# IO_Board.net
KiCad netlist of a schematic drawn in EAGLE
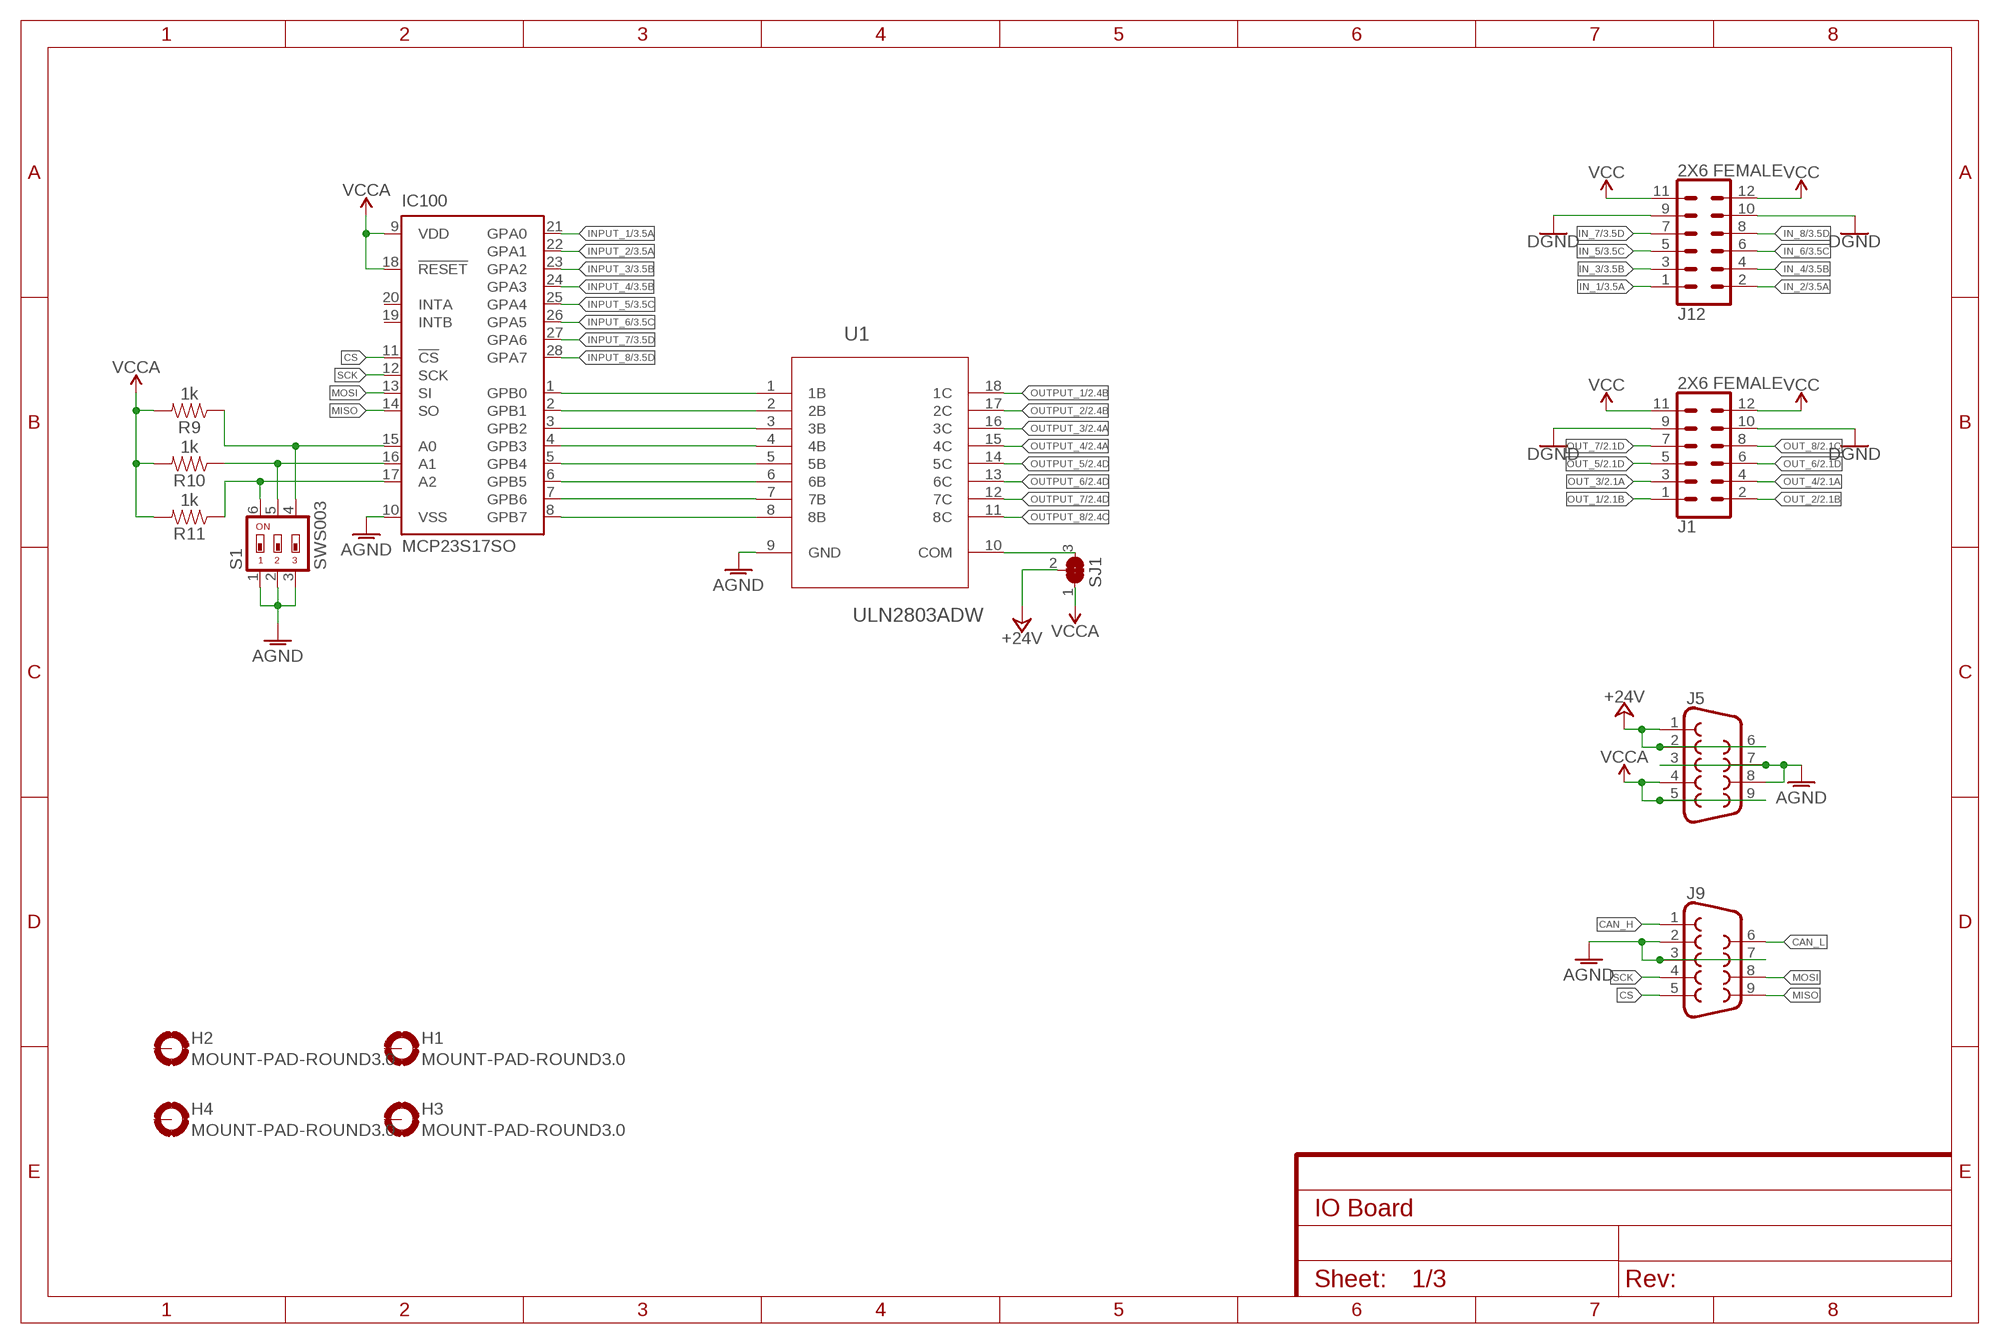
[diagram p0: schematic, sheet 1]
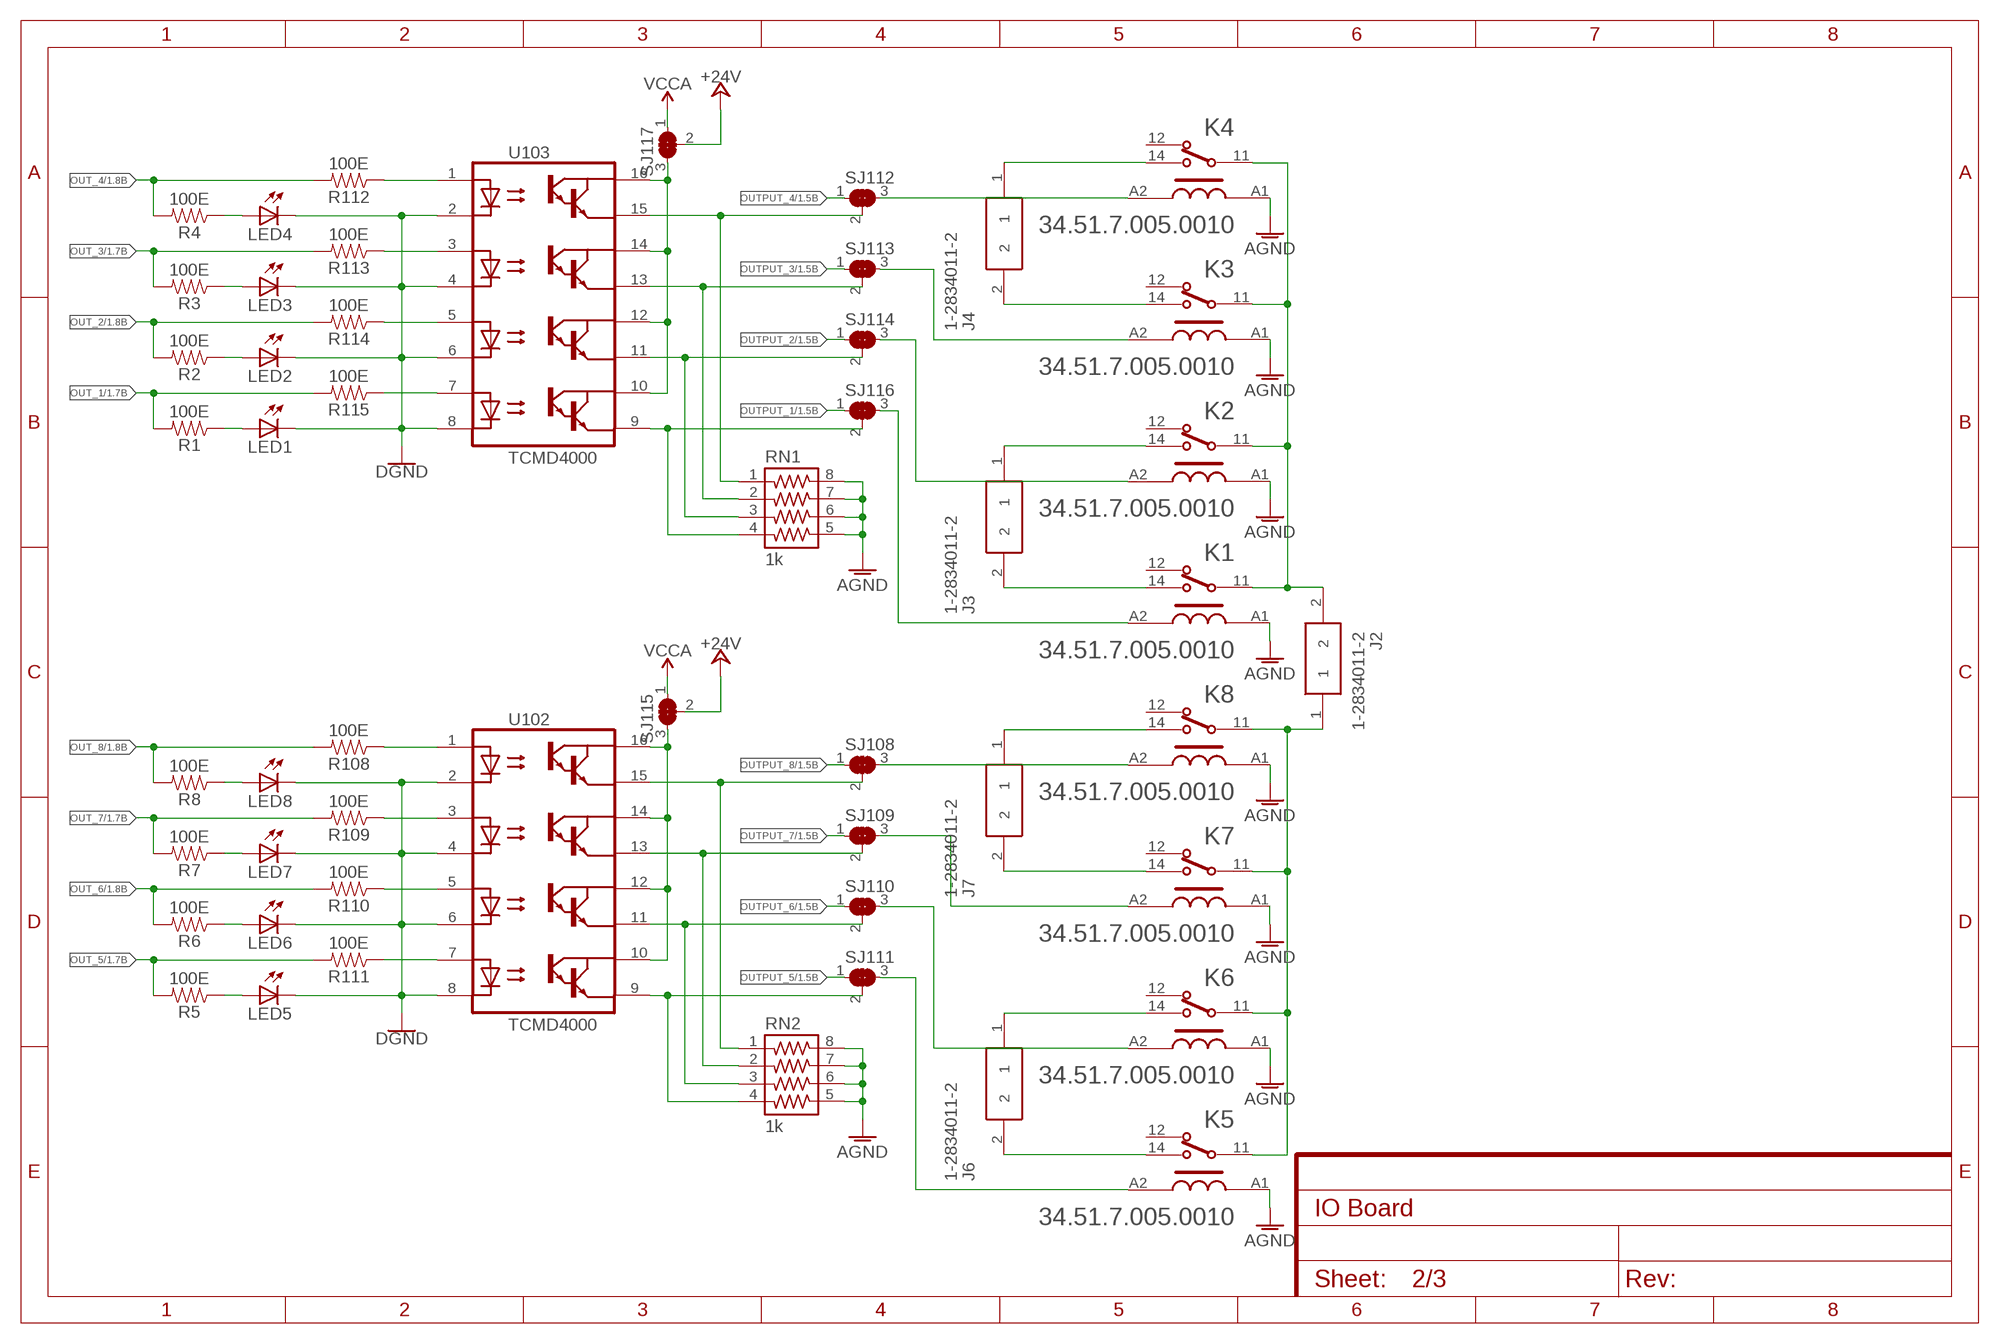
[diagram p1: schematic, sheet 2]
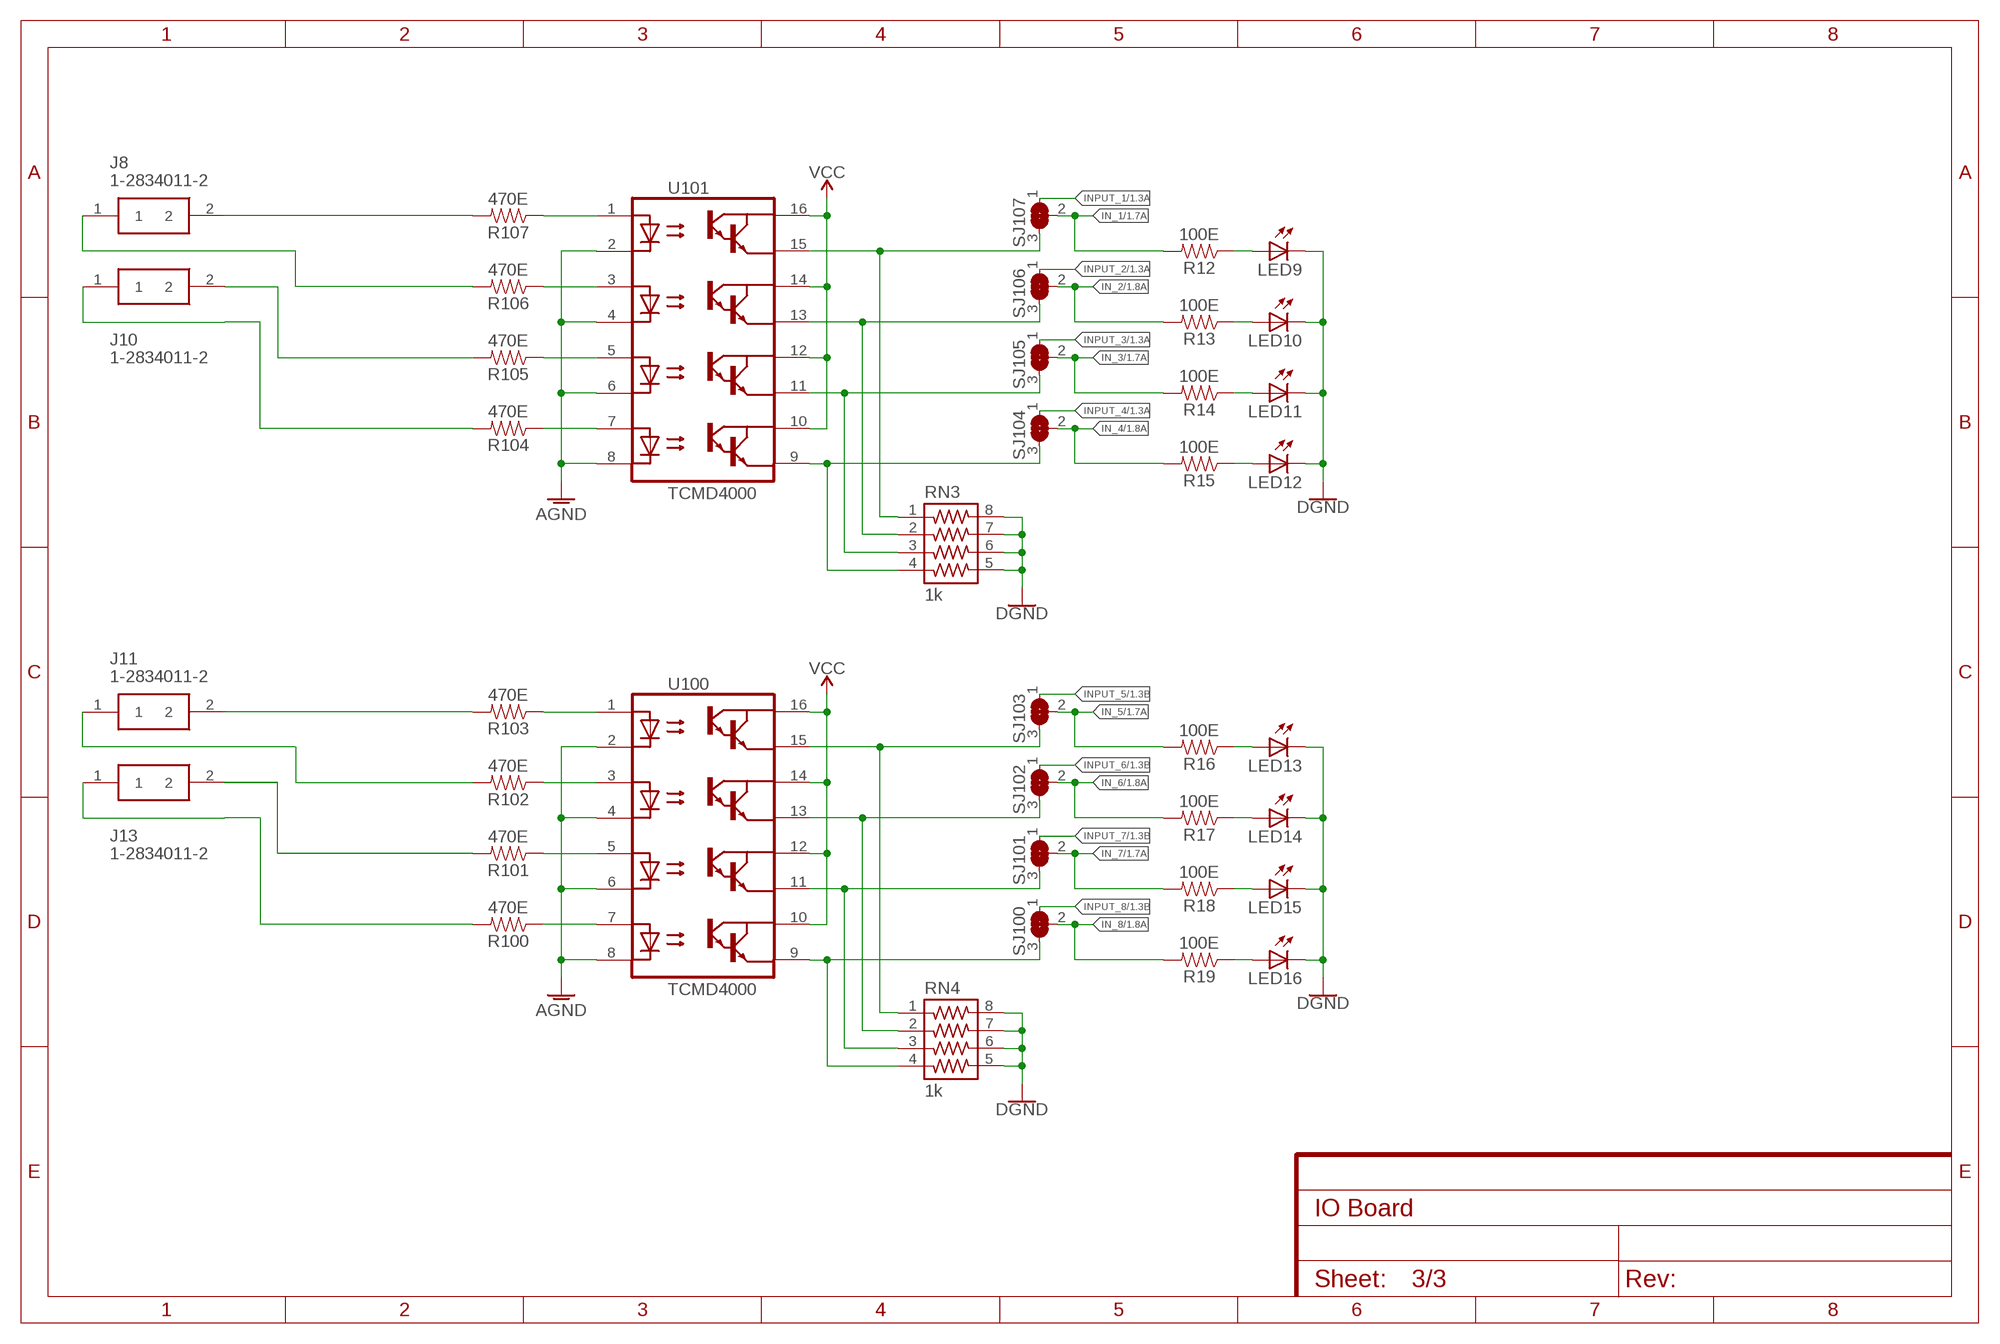
[diagram p2: schematic, sheet 3]

(export (version "E")
  (design (tool "Eeschema 10.0.6"))
  (components
    (comp (ref "H1")
      (value "MOUNT-PAD-ROUND3.0")
      (footprint "eagle-import:3,0-PAD")
      (libsource (lib "eagle-import") (part "MOUNT-PAD-ROUND3.0"))
    )
    (comp (ref "H2")
      (value "MOUNT-PAD-ROUND3.0")
      (footprint "eagle-import:3,0-PAD")
      (libsource (lib "eagle-import") (part "MOUNT-PAD-ROUND3.0"))
    )
    (comp (ref "H3")
      (value "MOUNT-PAD-ROUND3.0")
      (footprint "eagle-import:3,0-PAD")
      (libsource (lib "eagle-import") (part "MOUNT-PAD-ROUND3.0"))
    )
    (comp (ref "H4")
      (value "MOUNT-PAD-ROUND3.0")
      (footprint "eagle-import:3,0-PAD")
      (libsource (lib "eagle-import") (part "MOUNT-PAD-ROUND3.0"))
    )
    (comp (ref "IC100")
      (value "MCP23S17SO")
      (footprint "eagle-import:SO28W")
      (fields (field (name "MF") "MICROCHIP") (field (name "MPN") "MCP23S17-E/SO"))
      (libsource (lib "eagle-import") (part "MCP23S17SO"))
    )
    (comp (ref "J1")
      (value "2X6 FEMALE")
      (footprint "eagle-import:2X6")
      (libsource (lib "eagle-import") (part "CONN_06X2PTH_FEMALE"))
    )
    (comp (ref "J5")
      (value "DB9FEMALE")
      (footprint "eagle-import:DB9")
      (libsource (lib "eagle-import") (part "DB9FEMALE"))
    )
    (comp (ref "J9")
      (value "DB9FEMALE")
      (footprint "eagle-import:DB9")
      (libsource (lib "eagle-import") (part "DB9FEMALE"))
    )
    (comp (ref "J12")
      (value "2X6 FEMALE")
      (footprint "eagle-import:2X6")
      (libsource (lib "eagle-import") (part "CONN_06X2PTH_FEMALE"))
    )
    (comp (ref "R9")
      (value "1k")
      (footprint "eagle-import:0805")
      (libsource (lib "eagle-import") (part "RESISTOR0805"))
    )
    (comp (ref "R10")
      (value "1k")
      (footprint "eagle-import:0805")
      (libsource (lib "eagle-import") (part "RESISTOR0805"))
    )
    (comp (ref "R11")
      (value "1k")
      (footprint "eagle-import:0805")
      (libsource (lib "eagle-import") (part "RESISTOR0805"))
    )
    (comp (ref "S1")
      (value "SWS003")
      (footprint "eagle-import:SMS-003")
      (libsource (lib "eagle-import") (part "SWS003"))
    )
    (comp (ref "SJ1")
      (value "SOLDERJUMPER_2WAY")
      (footprint "eagle-import:SOLDERJUMPER_2WAY_OPEN_NOPASTE")
      (libsource (lib "eagle-import") (part "SOLDERJUMPER_2WAY"))
    )
    (comp (ref "U1")
      (value "ULN2803ADW")
      (footprint "eagle-import:SOIC127P1030X265-18N")
      (libsource (lib "eagle-import") (part "ULN2803ADW"))
    )
    (comp (ref "J8")
      (value "1-2834011-2")
      (footprint "eagle-import:128340112")
      (fields (field (name "RS_PART_NUMBER") "1649131"))
      (libsource (lib "eagle-import") (part "1-2834011-2"))
    )
    (comp (ref "J10")
      (value "1-2834011-2")
      (footprint "eagle-import:128340112")
      (fields (field (name "RS_PART_NUMBER") "1649131"))
      (libsource (lib "eagle-import") (part "1-2834011-2"))
    )
    (comp (ref "J11")
      (value "1-2834011-2")
      (footprint "eagle-import:128340112")
      (fields (field (name "RS_PART_NUMBER") "1649131"))
      (libsource (lib "eagle-import") (part "1-2834011-2"))
    )
    (comp (ref "J13")
      (value "1-2834011-2")
      (footprint "eagle-import:128340112")
      (fields (field (name "RS_PART_NUMBER") "1649131"))
      (libsource (lib "eagle-import") (part "1-2834011-2"))
    )
    (comp (ref "LED9")
      (value "LEDCHIP-LED0805")
      (footprint "eagle-import:CHIP-LED0805")
      (libsource (lib "eagle-import") (part "LEDCHIP-LED0805"))
    )
    (comp (ref "LED10")
      (value "LEDCHIP-LED0805")
      (footprint "eagle-import:CHIP-LED0805")
      (libsource (lib "eagle-import") (part "LEDCHIP-LED0805"))
    )
    (comp (ref "LED11")
      (value "LEDCHIP-LED0805")
      (footprint "eagle-import:CHIP-LED0805")
      (libsource (lib "eagle-import") (part "LEDCHIP-LED0805"))
    )
    (comp (ref "LED12")
      (value "LEDCHIP-LED0805")
      (footprint "eagle-import:CHIP-LED0805")
      (libsource (lib "eagle-import") (part "LEDCHIP-LED0805"))
    )
    (comp (ref "LED13")
      (value "LEDCHIP-LED0805")
      (footprint "eagle-import:CHIP-LED0805")
      (libsource (lib "eagle-import") (part "LEDCHIP-LED0805"))
    )
    (comp (ref "LED14")
      (value "LEDCHIP-LED0805")
      (footprint "eagle-import:CHIP-LED0805")
      (libsource (lib "eagle-import") (part "LEDCHIP-LED0805"))
    )
    (comp (ref "LED15")
      (value "LEDCHIP-LED0805")
      (footprint "eagle-import:CHIP-LED0805")
      (libsource (lib "eagle-import") (part "LEDCHIP-LED0805"))
    )
    (comp (ref "LED16")
      (value "LEDCHIP-LED0805")
      (footprint "eagle-import:CHIP-LED0805")
      (libsource (lib "eagle-import") (part "LEDCHIP-LED0805"))
    )
    (comp (ref "R12")
      (value "100E")
      (footprint "eagle-import:0805")
      (libsource (lib "eagle-import") (part "RESISTOR0805"))
    )
    (comp (ref "R13")
      (value "100E")
      (footprint "eagle-import:0805")
      (libsource (lib "eagle-import") (part "RESISTOR0805"))
    )
    (comp (ref "R14")
      (value "100E")
      (footprint "eagle-import:0805")
      (libsource (lib "eagle-import") (part "RESISTOR0805"))
    )
    (comp (ref "R15")
      (value "100E")
      (footprint "eagle-import:0805")
      (libsource (lib "eagle-import") (part "RESISTOR0805"))
    )
    (comp (ref "R16")
      (value "100E")
      (footprint "eagle-import:0805")
      (libsource (lib "eagle-import") (part "RESISTOR0805"))
    )
    (comp (ref "R17")
      (value "100E")
      (footprint "eagle-import:0805")
      (libsource (lib "eagle-import") (part "RESISTOR0805"))
    )
    (comp (ref "R18")
      (value "100E")
      (footprint "eagle-import:0805")
      (libsource (lib "eagle-import") (part "RESISTOR0805"))
    )
    (comp (ref "R19")
      (value "100E")
      (footprint "eagle-import:0805")
      (libsource (lib "eagle-import") (part "RESISTOR0805"))
    )
    (comp (ref "R100")
      (value "470E")
      (footprint "eagle-import:0805")
      (libsource (lib "eagle-import") (part "RESISTOR0805"))
    )
    (comp (ref "R101")
      (value "470E")
      (footprint "eagle-import:0805")
      (libsource (lib "eagle-import") (part "RESISTOR0805"))
    )
    (comp (ref "R102")
      (value "470E")
      (footprint "eagle-import:0805")
      (libsource (lib "eagle-import") (part "RESISTOR0805"))
    )
    (comp (ref "R103")
      (value "470E")
      (footprint "eagle-import:0805")
      (libsource (lib "eagle-import") (part "RESISTOR0805"))
    )
    (comp (ref "R104")
      (value "470E")
      (footprint "eagle-import:0805")
      (libsource (lib "eagle-import") (part "RESISTOR0805"))
    )
    (comp (ref "R105")
      (value "470E")
      (footprint "eagle-import:0805")
      (libsource (lib "eagle-import") (part "RESISTOR0805"))
    )
    (comp (ref "R106")
      (value "470E")
      (footprint "eagle-import:0805")
      (libsource (lib "eagle-import") (part "RESISTOR0805"))
    )
    (comp (ref "R107")
      (value "470E")
      (footprint "eagle-import:0805")
      (libsource (lib "eagle-import") (part "RESISTOR0805"))
    )
    (comp (ref "RN3")
      (value "1k")
      (footprint "eagle-import:743-8NS")
      (libsource (lib "eagle-import") (part "743-8NS"))
    )
    (comp (ref "RN4")
      (value "1k")
      (footprint "eagle-import:743-8NS")
      (libsource (lib "eagle-import") (part "743-8NS"))
    )
    (comp (ref "SJ100")
      (value "SOLDERJUMPER_2WAY")
      (footprint "eagle-import:SOLDERJUMPER_2WAY_OPEN_NOPASTE")
      (libsource (lib "eagle-import") (part "SOLDERJUMPER_2WAY"))
    )
    (comp (ref "SJ101")
      (value "SOLDERJUMPER_2WAY")
      (footprint "eagle-import:SOLDERJUMPER_2WAY_OPEN_NOPASTE")
      (libsource (lib "eagle-import") (part "SOLDERJUMPER_2WAY"))
    )
    (comp (ref "SJ102")
      (value "SOLDERJUMPER_2WAY")
      (footprint "eagle-import:SOLDERJUMPER_2WAY_OPEN_NOPASTE")
      (libsource (lib "eagle-import") (part "SOLDERJUMPER_2WAY"))
    )
    (comp (ref "SJ103")
      (value "SOLDERJUMPER_2WAY")
      (footprint "eagle-import:SOLDERJUMPER_2WAY_OPEN_NOPASTE")
      (libsource (lib "eagle-import") (part "SOLDERJUMPER_2WAY"))
    )
    (comp (ref "SJ104")
      (value "SOLDERJUMPER_2WAY")
      (footprint "eagle-import:SOLDERJUMPER_2WAY_OPEN_NOPASTE")
      (libsource (lib "eagle-import") (part "SOLDERJUMPER_2WAY"))
    )
    (comp (ref "SJ105")
      (value "SOLDERJUMPER_2WAY")
      (footprint "eagle-import:SOLDERJUMPER_2WAY_OPEN_NOPASTE")
      (libsource (lib "eagle-import") (part "SOLDERJUMPER_2WAY"))
    )
    (comp (ref "SJ106")
      (value "SOLDERJUMPER_2WAY")
      (footprint "eagle-import:SOLDERJUMPER_2WAY_OPEN_NOPASTE")
      (libsource (lib "eagle-import") (part "SOLDERJUMPER_2WAY"))
    )
    (comp (ref "SJ107")
      (value "SOLDERJUMPER_2WAY")
      (footprint "eagle-import:SOLDERJUMPER_2WAY_OPEN_NOPASTE")
      (libsource (lib "eagle-import") (part "SOLDERJUMPER_2WAY"))
    )
    (comp (ref "U100")
      (value "TCMD4000")
      (footprint "eagle-import:SOIC127P686X201-16N")
      (fields (field (name "MF") "Vishay Semiconductor"))
      (libsource (lib "eagle-import") (part "TCMD4000"))
    )
    (comp (ref "U101")
      (value "TCMD4000")
      (footprint "eagle-import:SOIC127P686X201-16N")
      (fields (field (name "MF") "Vishay Semiconductor"))
      (libsource (lib "eagle-import") (part "TCMD4000"))
    )
    (comp (ref "J2")
      (value "1-2834011-2")
      (footprint "eagle-import:128340112")
      (fields (field (name "RS_PART_NUMBER") "1649131"))
      (libsource (lib "eagle-import") (part "1-2834011-2"))
    )
    (comp (ref "J3")
      (value "1-2834011-2")
      (footprint "eagle-import:128340112")
      (fields (field (name "RS_PART_NUMBER") "1649131"))
      (libsource (lib "eagle-import") (part "1-2834011-2"))
    )
    (comp (ref "J4")
      (value "1-2834011-2")
      (footprint "eagle-import:128340112")
      (fields (field (name "RS_PART_NUMBER") "1649131"))
      (libsource (lib "eagle-import") (part "1-2834011-2"))
    )
    (comp (ref "J6")
      (value "1-2834011-2")
      (footprint "eagle-import:128340112")
      (fields (field (name "RS_PART_NUMBER") "1649131"))
      (libsource (lib "eagle-import") (part "1-2834011-2"))
    )
    (comp (ref "J7")
      (value "1-2834011-2")
      (footprint "eagle-import:128340112")
      (fields (field (name "RS_PART_NUMBER") "1649131"))
      (libsource (lib "eagle-import") (part "1-2834011-2"))
    )
    (comp (ref "K1")
      (value "FINDER_34.51.7.005.0010FINDER_34.51.7.005.0010_0_0")
      (footprint "eagle-import:FINDER_34.51.7.005.0010_0")
      (fields (field (name "MF") "Finder") (field (name "MPN") "34.51.7.005.0010"))
      (libsource (lib "eagle-import") (part "FINDER_34.51.7.005.0010FINDER_34.51.7.005.0010_0_0"))
    )
    (comp (ref "K2")
      (value "FINDER_34.51.7.005.0010FINDER_34.51.7.005.0010_0_0")
      (footprint "eagle-import:FINDER_34.51.7.005.0010_0")
      (fields (field (name "MF") "Finder") (field (name "MPN") "34.51.7.005.0010"))
      (libsource (lib "eagle-import") (part "FINDER_34.51.7.005.0010FINDER_34.51.7.005.0010_0_0"))
    )
    (comp (ref "K3")
      (value "FINDER_34.51.7.005.0010FINDER_34.51.7.005.0010_0_0")
      (footprint "eagle-import:FINDER_34.51.7.005.0010_0")
      (fields (field (name "MF") "Finder") (field (name "MPN") "34.51.7.005.0010"))
      (libsource (lib "eagle-import") (part "FINDER_34.51.7.005.0010FINDER_34.51.7.005.0010_0_0"))
    )
    (comp (ref "K4")
      (value "FINDER_34.51.7.005.0010FINDER_34.51.7.005.0010_0_0")
      (footprint "eagle-import:FINDER_34.51.7.005.0010_0")
      (fields (field (name "MF") "Finder") (field (name "MPN") "34.51.7.005.0010"))
      (libsource (lib "eagle-import") (part "FINDER_34.51.7.005.0010FINDER_34.51.7.005.0010_0_0"))
    )
    (comp (ref "K5")
      (value "FINDER_34.51.7.005.0010FINDER_34.51.7.005.0010_0_0")
      (footprint "eagle-import:FINDER_34.51.7.005.0010_0")
      (fields (field (name "MF") "Finder") (field (name "MPN") "34.51.7.005.0010"))
      (libsource (lib "eagle-import") (part "FINDER_34.51.7.005.0010FINDER_34.51.7.005.0010_0_0"))
    )
    (comp (ref "K6")
      (value "FINDER_34.51.7.005.0010FINDER_34.51.7.005.0010_0_0")
      (footprint "eagle-import:FINDER_34.51.7.005.0010_0")
      (fields (field (name "MF") "Finder") (field (name "MPN") "34.51.7.005.0010"))
      (libsource (lib "eagle-import") (part "FINDER_34.51.7.005.0010FINDER_34.51.7.005.0010_0_0"))
    )
    (comp (ref "K7")
      (value "FINDER_34.51.7.005.0010FINDER_34.51.7.005.0010_0_0")
      (footprint "eagle-import:FINDER_34.51.7.005.0010_0")
      (fields (field (name "MF") "Finder") (field (name "MPN") "34.51.7.005.0010"))
      (libsource (lib "eagle-import") (part "FINDER_34.51.7.005.0010FINDER_34.51.7.005.0010_0_0"))
    )
    (comp (ref "K8")
      (value "FINDER_34.51.7.005.0010FINDER_34.51.7.005.0010_0_0")
      (footprint "eagle-import:FINDER_34.51.7.005.0010_0")
      (fields (field (name "MF") "Finder") (field (name "MPN") "34.51.7.005.0010"))
      (libsource (lib "eagle-import") (part "FINDER_34.51.7.005.0010FINDER_34.51.7.005.0010_0_0"))
    )
    (comp (ref "LED1")
      (value "LEDCHIP-LED0805")
      (footprint "eagle-import:CHIP-LED0805")
      (libsource (lib "eagle-import") (part "LEDCHIP-LED0805"))
    )
    (comp (ref "LED2")
      (value "LEDCHIP-LED0805")
      (footprint "eagle-import:CHIP-LED0805")
      (libsource (lib "eagle-import") (part "LEDCHIP-LED0805"))
    )
    (comp (ref "LED3")
      (value "LEDCHIP-LED0805")
      (footprint "eagle-import:CHIP-LED0805")
      (libsource (lib "eagle-import") (part "LEDCHIP-LED0805"))
    )
    (comp (ref "LED4")
      (value "LEDCHIP-LED0805")
      (footprint "eagle-import:CHIP-LED0805")
      (libsource (lib "eagle-import") (part "LEDCHIP-LED0805"))
    )
    (comp (ref "LED5")
      (value "LEDCHIP-LED0805")
      (footprint "eagle-import:CHIP-LED0805")
      (libsource (lib "eagle-import") (part "LEDCHIP-LED0805"))
    )
    (comp (ref "LED6")
      (value "LEDCHIP-LED0805")
      (footprint "eagle-import:CHIP-LED0805")
      (libsource (lib "eagle-import") (part "LEDCHIP-LED0805"))
    )
    (comp (ref "LED7")
      (value "LEDCHIP-LED0805")
      (footprint "eagle-import:CHIP-LED0805")
      (libsource (lib "eagle-import") (part "LEDCHIP-LED0805"))
    )
    (comp (ref "LED8")
      (value "LEDCHIP-LED0805")
      (footprint "eagle-import:CHIP-LED0805")
      (libsource (lib "eagle-import") (part "LEDCHIP-LED0805"))
    )
    (comp (ref "R1")
      (value "100E")
      (footprint "eagle-import:0805")
      (libsource (lib "eagle-import") (part "RESISTOR0805"))
    )
    (comp (ref "R2")
      (value "100E")
      (footprint "eagle-import:0805")
      (libsource (lib "eagle-import") (part "RESISTOR0805"))
    )
    (comp (ref "R3")
      (value "100E")
      (footprint "eagle-import:0805")
      (libsource (lib "eagle-import") (part "RESISTOR0805"))
    )
    (comp (ref "R4")
      (value "100E")
      (footprint "eagle-import:0805")
      (libsource (lib "eagle-import") (part "RESISTOR0805"))
    )
    (comp (ref "R5")
      (value "100E")
      (footprint "eagle-import:0805")
      (libsource (lib "eagle-import") (part "RESISTOR0805"))
    )
    (comp (ref "R6")
      (value "100E")
      (footprint "eagle-import:0805")
      (libsource (lib "eagle-import") (part "RESISTOR0805"))
    )
    (comp (ref "R7")
      (value "100E")
      (footprint "eagle-import:0805")
      (libsource (lib "eagle-import") (part "RESISTOR0805"))
    )
    (comp (ref "R8")
      (value "100E")
      (footprint "eagle-import:0805")
      (libsource (lib "eagle-import") (part "RESISTOR0805"))
    )
    (comp (ref "R108")
      (value "100E")
      (footprint "eagle-import:0805")
      (libsource (lib "eagle-import") (part "RESISTOR0805"))
    )
    (comp (ref "R109")
      (value "100E")
      (footprint "eagle-import:0805")
      (libsource (lib "eagle-import") (part "RESISTOR0805"))
    )
    (comp (ref "R110")
      (value "100E")
      (footprint "eagle-import:0805")
      (libsource (lib "eagle-import") (part "RESISTOR0805"))
    )
    (comp (ref "R111")
      (value "100E")
      (footprint "eagle-import:0805")
      (libsource (lib "eagle-import") (part "RESISTOR0805"))
    )
    (comp (ref "R112")
      (value "100E")
      (footprint "eagle-import:0805")
      (libsource (lib "eagle-import") (part "RESISTOR0805"))
    )
    (comp (ref "R113")
      (value "100E")
      (footprint "eagle-import:0805")
      (libsource (lib "eagle-import") (part "RESISTOR0805"))
    )
    (comp (ref "R114")
      (value "100E")
      (footprint "eagle-import:0805")
      (libsource (lib "eagle-import") (part "RESISTOR0805"))
    )
    (comp (ref "R115")
      (value "100E")
      (footprint "eagle-import:0805")
      (libsource (lib "eagle-import") (part "RESISTOR0805"))
    )
    (comp (ref "RN1")
      (value "1k")
      (footprint "eagle-import:743-8NS")
      (libsource (lib "eagle-import") (part "743-8NS"))
    )
    (comp (ref "RN2")
      (value "1k")
      (footprint "eagle-import:743-8NS")
      (libsource (lib "eagle-import") (part "743-8NS"))
    )
    (comp (ref "SJ108")
      (value "SOLDERJUMPER_2WAY")
      (footprint "eagle-import:SOLDERJUMPER_2WAY_OPEN_NOPASTE")
      (libsource (lib "eagle-import") (part "SOLDERJUMPER_2WAY"))
    )
    (comp (ref "SJ109")
      (value "SOLDERJUMPER_2WAY")
      (footprint "eagle-import:SOLDERJUMPER_2WAY_OPEN_NOPASTE")
      (libsource (lib "eagle-import") (part "SOLDERJUMPER_2WAY"))
    )
    (comp (ref "SJ110")
      (value "SOLDERJUMPER_2WAY")
      (footprint "eagle-import:SOLDERJUMPER_2WAY_OPEN_NOPASTE")
      (libsource (lib "eagle-import") (part "SOLDERJUMPER_2WAY"))
    )
    (comp (ref "SJ111")
      (value "SOLDERJUMPER_2WAY")
      (footprint "eagle-import:SOLDERJUMPER_2WAY_OPEN_NOPASTE")
      (libsource (lib "eagle-import") (part "SOLDERJUMPER_2WAY"))
    )
    (comp (ref "SJ112")
      (value "SOLDERJUMPER_2WAY")
      (footprint "eagle-import:SOLDERJUMPER_2WAY_OPEN_NOPASTE")
      (libsource (lib "eagle-import") (part "SOLDERJUMPER_2WAY"))
    )
    (comp (ref "SJ113")
      (value "SOLDERJUMPER_2WAY")
      (footprint "eagle-import:SOLDERJUMPER_2WAY_OPEN_NOPASTE")
      (libsource (lib "eagle-import") (part "SOLDERJUMPER_2WAY"))
    )
    (comp (ref "SJ114")
      (value "SOLDERJUMPER_2WAY")
      (footprint "eagle-import:SOLDERJUMPER_2WAY_OPEN_NOPASTE")
      (libsource (lib "eagle-import") (part "SOLDERJUMPER_2WAY"))
    )
    (comp (ref "SJ115")
      (value "SOLDERJUMPER_2WAY")
      (footprint "eagle-import:SOLDERJUMPER_2WAY_OPEN_NOPASTE")
      (libsource (lib "eagle-import") (part "SOLDERJUMPER_2WAY"))
    )
    (comp (ref "SJ116")
      (value "SOLDERJUMPER_2WAY")
      (footprint "eagle-import:SOLDERJUMPER_2WAY_OPEN_NOPASTE")
      (libsource (lib "eagle-import") (part "SOLDERJUMPER_2WAY"))
    )
    (comp (ref "SJ117")
      (value "SOLDERJUMPER_2WAY")
      (footprint "eagle-import:SOLDERJUMPER_2WAY_OPEN_NOPASTE")
      (libsource (lib "eagle-import") (part "SOLDERJUMPER_2WAY"))
    )
    (comp (ref "U102")
      (value "TCMD4000")
      (footprint "eagle-import:SOIC127P686X201-16N")
      (fields (field (name "MF") "Vishay Semiconductor"))
      (libsource (lib "eagle-import") (part "TCMD4000"))
    )
    (comp (ref "U103")
      (value "TCMD4000")
      (footprint "eagle-import:SOIC127P686X201-16N")
      (fields (field (name "MF") "Vishay Semiconductor"))
      (libsource (lib "eagle-import") (part "TCMD4000"))
    )
  )
  (nets
    (net (code "1") (name "+24V") (class "Default")
      (node (ref "J5") (pin "1") (pinfunction "1_1") (pintype "passive"))
      (node (ref "J5") (pin "2") (pinfunction "2_2") (pintype "passive"))
      (node (ref "J5") (pin "6") (pinfunction "6_6") (pintype "passive"))
      (node (ref "SJ1") (pin "2") (pinfunction "2_2") (pintype "passive"))
      (node (ref "SJ115") (pin "2") (pinfunction "2_2") (pintype "passive"))
      (node (ref "SJ117") (pin "2") (pinfunction "2_2") (pintype "passive"))
    )
    (net (code "2") (name "AGND") (class "Default")
      (node (ref "IC100") (pin "10") (pinfunction "VSS_10") (pintype "power_in"))
      (node (ref "J5") (pin "3") (pinfunction "3_3") (pintype "passive"))
      (node (ref "J5") (pin "7") (pinfunction "7_7") (pintype "passive"))
      (node (ref "J5") (pin "8") (pinfunction "8_8") (pintype "passive"))
      (node (ref "J9") (pin "2") (pinfunction "2_2") (pintype "passive"))
      (node (ref "J9") (pin "3") (pinfunction "3_3") (pintype "passive"))
      (node (ref "J9") (pin "7") (pinfunction "7_7") (pintype "passive"))
      (node (ref "K1") (pin "A1") (pinfunction "A1_A1") (pintype "passive"))
      (node (ref "K2") (pin "A1") (pinfunction "A1_A1") (pintype "passive"))
      (node (ref "K3") (pin "A1") (pinfunction "A1_A1") (pintype "passive"))
      (node (ref "K4") (pin "A1") (pinfunction "A1_A1") (pintype "passive"))
      (node (ref "K5") (pin "A1") (pinfunction "A1_A1") (pintype "passive"))
      (node (ref "K6") (pin "A1") (pinfunction "A1_A1") (pintype "passive"))
      (node (ref "K7") (pin "A1") (pinfunction "A1_A1") (pintype "passive"))
      (node (ref "K8") (pin "A1") (pinfunction "A1_A1") (pintype "passive"))
      (node (ref "RN1") (pin "5") (pinfunction "5_5") (pintype "passive"))
      (node (ref "RN1") (pin "6") (pinfunction "6_6") (pintype "passive"))
      (node (ref "RN1") (pin "7") (pinfunction "7_7") (pintype "passive"))
      (node (ref "RN1") (pin "8") (pinfunction "8_8") (pintype "passive"))
      (node (ref "RN2") (pin "5") (pinfunction "5_5") (pintype "passive"))
      (node (ref "RN2") (pin "6") (pinfunction "6_6") (pintype "passive"))
      (node (ref "RN2") (pin "7") (pinfunction "7_7") (pintype "passive"))
      (node (ref "RN2") (pin "8") (pinfunction "8_8") (pintype "passive"))
      (node (ref "S1") (pin "1") (pinfunction "1_1") (pintype "passive"))
      (node (ref "S1") (pin "2") (pinfunction "2_2") (pintype "passive"))
      (node (ref "S1") (pin "3") (pinfunction "3_3") (pintype "passive"))
      (node (ref "U1") (pin "9") (pinfunction "GND_9") (pintype "passive"))
      (node (ref "U100") (pin "2") (pinfunction "C1_2") (pintype "passive"))
      (node (ref "U100") (pin "4") (pinfunction "C2_4") (pintype "passive"))
      (node (ref "U100") (pin "6") (pinfunction "C3_6") (pintype "passive"))
      (node (ref "U100") (pin "8") (pinfunction "C4_8") (pintype "passive"))
      (node (ref "U101") (pin "2") (pinfunction "C1_2") (pintype "passive"))
      (node (ref "U101") (pin "4") (pinfunction "C2_4") (pintype "passive"))
      (node (ref "U101") (pin "6") (pinfunction "C3_6") (pintype "passive"))
      (node (ref "U101") (pin "8") (pinfunction "C4_8") (pintype "passive"))
    )
    (net (code "3") (name "CAN_H") (class "Default")
      (node (ref "J9") (pin "1") (pinfunction "1_1") (pintype "passive"))
    )
    (net (code "4") (name "CAN_L") (class "Default")
      (node (ref "J9") (pin "6") (pinfunction "6_6") (pintype "passive"))
    )
    (net (code "5") (name "CS") (class "Default")
      (node (ref "IC100") (pin "11") (pinfunction "~{CS}_11") (pintype "input"))
      (node (ref "J9") (pin "5") (pinfunction "5_5") (pintype "passive"))
    )
    (net (code "6") (name "GND") (class "Default")
      (node (ref "J1") (pin "10") (pinfunction "10_10") (pintype "passive"))
      (node (ref "J1") (pin "9") (pinfunction "9_9") (pintype "passive"))
      (node (ref "J12") (pin "10") (pinfunction "10_10") (pintype "passive"))
      (node (ref "J12") (pin "9") (pinfunction "9_9") (pintype "passive"))
      (node (ref "LED1") (pin "C") (pinfunction "C_C") (pintype "passive"))
      (node (ref "LED10") (pin "C") (pinfunction "C_C") (pintype "passive"))
      (node (ref "LED11") (pin "C") (pinfunction "C_C") (pintype "passive"))
      (node (ref "LED12") (pin "C") (pinfunction "C_C") (pintype "passive"))
      (node (ref "LED13") (pin "C") (pinfunction "C_C") (pintype "passive"))
      (node (ref "LED14") (pin "C") (pinfunction "C_C") (pintype "passive"))
      (node (ref "LED15") (pin "C") (pinfunction "C_C") (pintype "passive"))
      (node (ref "LED16") (pin "C") (pinfunction "C_C") (pintype "passive"))
      (node (ref "LED2") (pin "C") (pinfunction "C_C") (pintype "passive"))
      (node (ref "LED3") (pin "C") (pinfunction "C_C") (pintype "passive"))
      (node (ref "LED4") (pin "C") (pinfunction "C_C") (pintype "passive"))
      (node (ref "LED5") (pin "C") (pinfunction "C_C") (pintype "passive"))
      (node (ref "LED6") (pin "C") (pinfunction "C_C") (pintype "passive"))
      (node (ref "LED7") (pin "C") (pinfunction "C_C") (pintype "passive"))
      (node (ref "LED8") (pin "C") (pinfunction "C_C") (pintype "passive"))
      (node (ref "LED9") (pin "C") (pinfunction "C_C") (pintype "passive"))
      (node (ref "RN3") (pin "5") (pinfunction "5_5") (pintype "passive"))
      (node (ref "RN3") (pin "6") (pinfunction "6_6") (pintype "passive"))
      (node (ref "RN3") (pin "7") (pinfunction "7_7") (pintype "passive"))
      (node (ref "RN3") (pin "8") (pinfunction "8_8") (pintype "passive"))
      (node (ref "RN4") (pin "5") (pinfunction "5_5") (pintype "passive"))
      (node (ref "RN4") (pin "6") (pinfunction "6_6") (pintype "passive"))
      (node (ref "RN4") (pin "7") (pinfunction "7_7") (pintype "passive"))
      (node (ref "RN4") (pin "8") (pinfunction "8_8") (pintype "passive"))
      (node (ref "U102") (pin "2") (pinfunction "C1_2") (pintype "passive"))
      (node (ref "U102") (pin "4") (pinfunction "C2_4") (pintype "passive"))
      (node (ref "U102") (pin "6") (pinfunction "C3_6") (pintype "passive"))
      (node (ref "U102") (pin "8") (pinfunction "C4_8") (pintype "passive"))
      (node (ref "U103") (pin "2") (pinfunction "C1_2") (pintype "passive"))
      (node (ref "U103") (pin "4") (pinfunction "C2_4") (pintype "passive"))
      (node (ref "U103") (pin "6") (pinfunction "C3_6") (pintype "passive"))
      (node (ref "U103") (pin "8") (pinfunction "C4_8") (pintype "passive"))
    )
    (net (code "7") (name "INPUT_1") (class "Default")
      (node (ref "IC100") (pin "21") (pinfunction "GPA0_21") (pintype "bidirectional"))
      (node (ref "SJ107") (pin "1") (pinfunction "1_1") (pintype "passive"))
    )
    (net (code "8") (name "INPUT_2") (class "Default")
      (node (ref "IC100") (pin "22") (pinfunction "GPA1_22") (pintype "bidirectional"))
      (node (ref "SJ106") (pin "1") (pinfunction "1_1") (pintype "passive"))
    )
    (net (code "9") (name "INPUT_3") (class "Default")
      (node (ref "IC100") (pin "23") (pinfunction "GPA2_23") (pintype "bidirectional"))
      (node (ref "SJ105") (pin "1") (pinfunction "1_1") (pintype "passive"))
    )
    (net (code "10") (name "INPUT_4") (class "Default")
      (node (ref "IC100") (pin "24") (pinfunction "GPA3_24") (pintype "bidirectional"))
      (node (ref "SJ104") (pin "1") (pinfunction "1_1") (pintype "passive"))
    )
    (net (code "11") (name "INPUT_5") (class "Default")
      (node (ref "IC100") (pin "25") (pinfunction "GPA4_25") (pintype "bidirectional"))
      (node (ref "SJ103") (pin "1") (pinfunction "1_1") (pintype "passive"))
    )
    (net (code "12") (name "INPUT_6") (class "Default")
      (node (ref "IC100") (pin "26") (pinfunction "GPA5_26") (pintype "bidirectional"))
      (node (ref "SJ102") (pin "1") (pinfunction "1_1") (pintype "passive"))
    )
    (net (code "13") (name "INPUT_7") (class "Default")
      (node (ref "IC100") (pin "27") (pinfunction "GPA6_27") (pintype "bidirectional"))
      (node (ref "SJ101") (pin "1") (pinfunction "1_1") (pintype "passive"))
    )
    (net (code "14") (name "INPUT_8") (class "Default")
      (node (ref "IC100") (pin "28") (pinfunction "GPA7_28") (pintype "bidirectional"))
      (node (ref "SJ100") (pin "1") (pinfunction "1_1") (pintype "passive"))
    )
    (net (code "15") (name "IN_1") (class "Default")
      (node (ref "J12") (pin "1") (pinfunction "1_1") (pintype "passive"))
      (node (ref "R12") (pin "2") (pinfunction "2_2") (pintype "passive"))
      (node (ref "SJ107") (pin "2") (pinfunction "2_2") (pintype "passive"))
    )
    (net (code "16") (name "IN_2") (class "Default")
      (node (ref "J12") (pin "2") (pinfunction "2_2") (pintype "passive"))
      (node (ref "R13") (pin "2") (pinfunction "2_2") (pintype "passive"))
      (node (ref "SJ106") (pin "2") (pinfunction "2_2") (pintype "passive"))
    )
    (net (code "17") (name "IN_3") (class "Default")
      (node (ref "J12") (pin "3") (pinfunction "3_3") (pintype "passive"))
      (node (ref "R14") (pin "2") (pinfunction "2_2") (pintype "passive"))
      (node (ref "SJ105") (pin "2") (pinfunction "2_2") (pintype "passive"))
    )
    (net (code "18") (name "IN_4") (class "Default")
      (node (ref "J12") (pin "4") (pinfunction "4_4") (pintype "passive"))
      (node (ref "R15") (pin "2") (pinfunction "2_2") (pintype "passive"))
      (node (ref "SJ104") (pin "2") (pinfunction "2_2") (pintype "passive"))
    )
    (net (code "19") (name "IN_5") (class "Default")
      (node (ref "J12") (pin "5") (pinfunction "5_5") (pintype "passive"))
      (node (ref "R16") (pin "2") (pinfunction "2_2") (pintype "passive"))
      (node (ref "SJ103") (pin "2") (pinfunction "2_2") (pintype "passive"))
    )
    (net (code "20") (name "IN_6") (class "Default")
      (node (ref "J12") (pin "6") (pinfunction "6_6") (pintype "passive"))
      (node (ref "R17") (pin "2") (pinfunction "2_2") (pintype "passive"))
      (node (ref "SJ102") (pin "2") (pinfunction "2_2") (pintype "passive"))
    )
    (net (code "21") (name "IN_7") (class "Default")
      (node (ref "J12") (pin "7") (pinfunction "7_7") (pintype "passive"))
      (node (ref "R18") (pin "2") (pinfunction "2_2") (pintype "passive"))
      (node (ref "SJ101") (pin "2") (pinfunction "2_2") (pintype "passive"))
    )
    (net (code "22") (name "IN_8") (class "Default")
      (node (ref "J12") (pin "8") (pinfunction "8_8") (pintype "passive"))
      (node (ref "R19") (pin "2") (pinfunction "2_2") (pintype "passive"))
      (node (ref "SJ100") (pin "2") (pinfunction "2_2") (pintype "passive"))
    )
    (net (code "23") (name "MISO") (class "Default")
      (node (ref "IC100") (pin "14") (pinfunction "SO_14") (pintype "output"))
      (node (ref "J9") (pin "9") (pinfunction "9_9") (pintype "passive"))
    )
    (net (code "24") (name "MOSI") (class "Default")
      (node (ref "IC100") (pin "13") (pinfunction "SI_13") (pintype "input"))
      (node (ref "J9") (pin "8") (pinfunction "8_8") (pintype "passive"))
    )
    (net (code "25") (name "Net-(IC100-A0)") (class "Default")
      (node (ref "IC100") (pin "15") (pinfunction "A0_15") (pintype "input"))
      (node (ref "R9") (pin "1") (pinfunction "1_1") (pintype "passive"))
      (node (ref "S1") (pin "4") (pinfunction "4_4") (pintype "passive"))
    )
    (net (code "26") (name "Net-(IC100-A1)") (class "Default")
      (node (ref "IC100") (pin "16") (pinfunction "A1_16") (pintype "input"))
      (node (ref "R10") (pin "1") (pinfunction "1_1") (pintype "passive"))
      (node (ref "S1") (pin "5") (pinfunction "5_5") (pintype "passive"))
    )
    (net (code "27") (name "Net-(IC100-A2)") (class "Default")
      (node (ref "IC100") (pin "17") (pinfunction "A2_17") (pintype "input"))
      (node (ref "R11") (pin "1") (pinfunction "1_1") (pintype "passive"))
      (node (ref "S1") (pin "6") (pinfunction "6_6") (pintype "passive"))
    )
    (net (code "28") (name "Net-(IC100-GPB0)") (class "Default")
      (node (ref "IC100") (pin "1") (pinfunction "GPB0_1") (pintype "bidirectional"))
      (node (ref "U1") (pin "1") (pinfunction "1B_1") (pintype "input"))
    )
    (net (code "29") (name "Net-(IC100-GPB1)") (class "Default")
      (node (ref "IC100") (pin "2") (pinfunction "GPB1_2") (pintype "bidirectional"))
      (node (ref "U1") (pin "2") (pinfunction "2B_2") (pintype "input"))
    )
    (net (code "30") (name "Net-(IC100-GPB2)") (class "Default")
      (node (ref "IC100") (pin "3") (pinfunction "GPB2_3") (pintype "bidirectional"))
      (node (ref "U1") (pin "3") (pinfunction "3B_3") (pintype "input"))
    )
    (net (code "31") (name "Net-(IC100-GPB3)") (class "Default")
      (node (ref "IC100") (pin "4") (pinfunction "GPB3_4") (pintype "bidirectional"))
      (node (ref "U1") (pin "4") (pinfunction "4B_4") (pintype "input"))
    )
    (net (code "32") (name "Net-(IC100-GPB4)") (class "Default")
      (node (ref "IC100") (pin "5") (pinfunction "GPB4_5") (pintype "bidirectional"))
      (node (ref "U1") (pin "5") (pinfunction "5B_5") (pintype "input"))
    )
    (net (code "33") (name "Net-(IC100-GPB5)") (class "Default")
      (node (ref "IC100") (pin "6") (pinfunction "GPB5_6") (pintype "bidirectional"))
      (node (ref "U1") (pin "6") (pinfunction "6B_6") (pintype "input"))
    )
    (net (code "34") (name "Net-(IC100-GPB6)") (class "Default")
      (node (ref "IC100") (pin "7") (pinfunction "GPB6_7") (pintype "bidirectional"))
      (node (ref "U1") (pin "7") (pinfunction "7B_7") (pintype "input"))
    )
    (net (code "35") (name "Net-(IC100-GPB7)") (class "Default")
      (node (ref "IC100") (pin "8") (pinfunction "GPB7_8") (pintype "bidirectional"))
      (node (ref "U1") (pin "8") (pinfunction "8B_8") (pintype "input"))
    )
    (net (code "36") (name "Net-(J2-Pad1)") (class "Default")
      (node (ref "J2") (pin "1") (pinfunction "1_1") (pintype "bidirectional"))
      (node (ref "K5") (pin "11") (pinfunction "11_11") (pintype "passive"))
      (node (ref "K6") (pin "11") (pinfunction "11_11") (pintype "passive"))
      (node (ref "K7") (pin "11") (pinfunction "11_11") (pintype "passive"))
      (node (ref "K8") (pin "11") (pinfunction "11_11") (pintype "passive"))
    )
    (net (code "37") (name "Net-(J2-Pad2)") (class "Default")
      (node (ref "J2") (pin "2") (pinfunction "2_2") (pintype "bidirectional"))
      (node (ref "K1") (pin "11") (pinfunction "11_11") (pintype "passive"))
      (node (ref "K2") (pin "11") (pinfunction "11_11") (pintype "passive"))
      (node (ref "K3") (pin "11") (pinfunction "11_11") (pintype "passive"))
      (node (ref "K4") (pin "11") (pinfunction "11_11") (pintype "passive"))
    )
    (net (code "38") (name "Net-(J3-Pad1)") (class "Default")
      (node (ref "J3") (pin "1") (pinfunction "1_1") (pintype "bidirectional"))
      (node (ref "K2") (pin "14") (pinfunction "14_14") (pintype "passive"))
    )
    (net (code "39") (name "Net-(J3-Pad2)") (class "Default")
      (node (ref "J3") (pin "2") (pinfunction "2_2") (pintype "bidirectional"))
      (node (ref "K1") (pin "14") (pinfunction "14_14") (pintype "passive"))
    )
    (net (code "40") (name "Net-(J4-Pad1)") (class "Default")
      (node (ref "J4") (pin "1") (pinfunction "1_1") (pintype "bidirectional"))
      (node (ref "K4") (pin "14") (pinfunction "14_14") (pintype "passive"))
    )
    (net (code "41") (name "Net-(J4-Pad2)") (class "Default")
      (node (ref "J4") (pin "2") (pinfunction "2_2") (pintype "bidirectional"))
      (node (ref "K3") (pin "14") (pinfunction "14_14") (pintype "passive"))
    )
    (net (code "42") (name "Net-(J6-Pad1)") (class "Default")
      (node (ref "J6") (pin "1") (pinfunction "1_1") (pintype "bidirectional"))
      (node (ref "K6") (pin "14") (pinfunction "14_14") (pintype "passive"))
    )
    (net (code "43") (name "Net-(J6-Pad2)") (class "Default")
      (node (ref "J6") (pin "2") (pinfunction "2_2") (pintype "bidirectional"))
      (node (ref "K5") (pin "14") (pinfunction "14_14") (pintype "passive"))
    )
    (net (code "44") (name "Net-(J7-Pad1)") (class "Default")
      (node (ref "J7") (pin "1") (pinfunction "1_1") (pintype "bidirectional"))
      (node (ref "K8") (pin "14") (pinfunction "14_14") (pintype "passive"))
    )
    (net (code "45") (name "Net-(J7-Pad2)") (class "Default")
      (node (ref "J7") (pin "2") (pinfunction "2_2") (pintype "bidirectional"))
      (node (ref "K7") (pin "14") (pinfunction "14_14") (pintype "passive"))
    )
    (net (code "46") (name "Net-(J8-Pad1)") (class "Default")
      (node (ref "J8") (pin "1") (pinfunction "1_1") (pintype "bidirectional"))
      (node (ref "R106") (pin "2") (pinfunction "2_2") (pintype "passive"))
    )
    (net (code "47") (name "Net-(J8-Pad2)") (class "Default")
      (node (ref "J8") (pin "2") (pinfunction "2_2") (pintype "bidirectional"))
      (node (ref "R107") (pin "2") (pinfunction "2_2") (pintype "passive"))
    )
    (net (code "48") (name "Net-(J10-Pad1)") (class "Default")
      (node (ref "J10") (pin "1") (pinfunction "1_1") (pintype "bidirectional"))
      (node (ref "R104") (pin "2") (pinfunction "2_2") (pintype "passive"))
    )
    (net (code "49") (name "Net-(J10-Pad2)") (class "Default")
      (node (ref "J10") (pin "2") (pinfunction "2_2") (pintype "bidirectional"))
      (node (ref "R105") (pin "2") (pinfunction "2_2") (pintype "passive"))
    )
    (net (code "50") (name "Net-(J11-Pad1)") (class "Default")
      (node (ref "J11") (pin "1") (pinfunction "1_1") (pintype "bidirectional"))
      (node (ref "R102") (pin "2") (pinfunction "2_2") (pintype "passive"))
    )
    (net (code "51") (name "Net-(J11-Pad2)") (class "Default")
      (node (ref "J11") (pin "2") (pinfunction "2_2") (pintype "bidirectional"))
      (node (ref "R103") (pin "2") (pinfunction "2_2") (pintype "passive"))
    )
    (net (code "52") (name "Net-(J13-Pad1)") (class "Default")
      (node (ref "J13") (pin "1") (pinfunction "1_1") (pintype "bidirectional"))
      (node (ref "R100") (pin "2") (pinfunction "2_2") (pintype "passive"))
    )
    (net (code "53") (name "Net-(J13-Pad2)") (class "Default")
      (node (ref "J13") (pin "2") (pinfunction "2_2") (pintype "bidirectional"))
      (node (ref "R101") (pin "2") (pinfunction "2_2") (pintype "passive"))
    )
    (net (code "54") (name "Net-(K1-PadA2)") (class "Default")
      (node (ref "K1") (pin "A2") (pinfunction "A2_A2") (pintype "passive"))
      (node (ref "SJ116") (pin "3") (pinfunction "3_3") (pintype "passive"))
    )
    (net (code "55") (name "Net-(K2-PadA2)") (class "Default")
      (node (ref "K2") (pin "A2") (pinfunction "A2_A2") (pintype "passive"))
      (node (ref "SJ114") (pin "3") (pinfunction "3_3") (pintype "passive"))
    )
    (net (code "56") (name "Net-(K3-PadA2)") (class "Default")
      (node (ref "K3") (pin "A2") (pinfunction "A2_A2") (pintype "passive"))
      (node (ref "SJ113") (pin "3") (pinfunction "3_3") (pintype "passive"))
    )
    (net (code "57") (name "Net-(K4-PadA2)") (class "Default")
      (node (ref "K4") (pin "A2") (pinfunction "A2_A2") (pintype "passive"))
      (node (ref "SJ112") (pin "3") (pinfunction "3_3") (pintype "passive"))
    )
    (net (code "58") (name "Net-(K5-PadA2)") (class "Default")
      (node (ref "K5") (pin "A2") (pinfunction "A2_A2") (pintype "passive"))
      (node (ref "SJ111") (pin "3") (pinfunction "3_3") (pintype "passive"))
    )
    (net (code "59") (name "Net-(K6-PadA2)") (class "Default")
      (node (ref "K6") (pin "A2") (pinfunction "A2_A2") (pintype "passive"))
      (node (ref "SJ110") (pin "3") (pinfunction "3_3") (pintype "passive"))
    )
    (net (code "60") (name "Net-(K7-PadA2)") (class "Default")
      (node (ref "K7") (pin "A2") (pinfunction "A2_A2") (pintype "passive"))
      (node (ref "SJ109") (pin "3") (pinfunction "3_3") (pintype "passive"))
    )
    (net (code "61") (name "Net-(K8-PadA2)") (class "Default")
      (node (ref "K8") (pin "A2") (pinfunction "A2_A2") (pintype "passive"))
      (node (ref "SJ108") (pin "3") (pinfunction "3_3") (pintype "passive"))
    )
    (net (code "62") (name "Net-(LED1-PadA)") (class "Default")
      (node (ref "LED1") (pin "A") (pinfunction "A_A") (pintype "passive"))
      (node (ref "R1") (pin "1") (pinfunction "1_1") (pintype "passive"))
    )
    (net (code "63") (name "Net-(LED2-PadA)") (class "Default")
      (node (ref "LED2") (pin "A") (pinfunction "A_A") (pintype "passive"))
      (node (ref "R2") (pin "1") (pinfunction "1_1") (pintype "passive"))
    )
    (net (code "64") (name "Net-(LED3-PadA)") (class "Default")
      (node (ref "LED3") (pin "A") (pinfunction "A_A") (pintype "passive"))
      (node (ref "R3") (pin "1") (pinfunction "1_1") (pintype "passive"))
    )
    (net (code "65") (name "Net-(LED4-PadA)") (class "Default")
      (node (ref "LED4") (pin "A") (pinfunction "A_A") (pintype "passive"))
      (node (ref "R4") (pin "1") (pinfunction "1_1") (pintype "passive"))
    )
    (net (code "66") (name "Net-(LED5-PadA)") (class "Default")
      (node (ref "LED5") (pin "A") (pinfunction "A_A") (pintype "passive"))
      (node (ref "R5") (pin "1") (pinfunction "1_1") (pintype "passive"))
    )
    (net (code "67") (name "Net-(LED6-PadA)") (class "Default")
      (node (ref "LED6") (pin "A") (pinfunction "A_A") (pintype "passive"))
      (node (ref "R6") (pin "1") (pinfunction "1_1") (pintype "passive"))
    )
    (net (code "68") (name "Net-(LED7-PadA)") (class "Default")
      (node (ref "LED7") (pin "A") (pinfunction "A_A") (pintype "passive"))
      (node (ref "R7") (pin "1") (pinfunction "1_1") (pintype "passive"))
    )
    (net (code "69") (name "Net-(LED8-PadA)") (class "Default")
      (node (ref "LED8") (pin "A") (pinfunction "A_A") (pintype "passive"))
      (node (ref "R8") (pin "1") (pinfunction "1_1") (pintype "passive"))
    )
    (net (code "70") (name "Net-(LED9-PadA)") (class "Default")
      (node (ref "LED9") (pin "A") (pinfunction "A_A") (pintype "passive"))
      (node (ref "R12") (pin "1") (pinfunction "1_1") (pintype "passive"))
    )
    (net (code "71") (name "Net-(LED10-PadA)") (class "Default")
      (node (ref "LED10") (pin "A") (pinfunction "A_A") (pintype "passive"))
      (node (ref "R13") (pin "1") (pinfunction "1_1") (pintype "passive"))
    )
    (net (code "72") (name "Net-(LED11-PadA)") (class "Default")
      (node (ref "LED11") (pin "A") (pinfunction "A_A") (pintype "passive"))
      (node (ref "R14") (pin "1") (pinfunction "1_1") (pintype "passive"))
    )
    (net (code "73") (name "Net-(LED12-PadA)") (class "Default")
      (node (ref "LED12") (pin "A") (pinfunction "A_A") (pintype "passive"))
      (node (ref "R15") (pin "1") (pinfunction "1_1") (pintype "passive"))
    )
    (net (code "74") (name "Net-(LED13-PadA)") (class "Default")
      (node (ref "LED13") (pin "A") (pinfunction "A_A") (pintype "passive"))
      (node (ref "R16") (pin "1") (pinfunction "1_1") (pintype "passive"))
    )
    (net (code "75") (name "Net-(LED14-PadA)") (class "Default")
      (node (ref "LED14") (pin "A") (pinfunction "A_A") (pintype "passive"))
      (node (ref "R17") (pin "1") (pinfunction "1_1") (pintype "passive"))
    )
    (net (code "76") (name "Net-(LED15-PadA)") (class "Default")
      (node (ref "LED15") (pin "A") (pinfunction "A_A") (pintype "passive"))
      (node (ref "R18") (pin "1") (pinfunction "1_1") (pintype "passive"))
    )
    (net (code "77") (name "Net-(LED16-PadA)") (class "Default")
      (node (ref "LED16") (pin "A") (pinfunction "A_A") (pintype "passive"))
      (node (ref "R19") (pin "1") (pinfunction "1_1") (pintype "passive"))
    )
    (net (code "78") (name "Net-(U1-COM)") (class "Default")
      (node (ref "SJ1") (pin "3") (pinfunction "3_3") (pintype "passive"))
      (node (ref "U1") (pin "10") (pinfunction "COM_10") (pintype "output"))
    )
    (net (code "79") (name "Net-(U100-A1)") (class "Default")
      (node (ref "R103") (pin "1") (pinfunction "1_1") (pintype "passive"))
      (node (ref "U100") (pin "1") (pinfunction "A1_1") (pintype "passive"))
    )
    (net (code "80") (name "Net-(U100-A2)") (class "Default")
      (node (ref "R102") (pin "1") (pinfunction "1_1") (pintype "passive"))
      (node (ref "U100") (pin "3") (pinfunction "A2_3") (pintype "passive"))
    )
    (net (code "81") (name "Net-(U100-A3)") (class "Default")
      (node (ref "R101") (pin "1") (pinfunction "1_1") (pintype "passive"))
      (node (ref "U100") (pin "5") (pinfunction "A3_5") (pintype "passive"))
    )
    (net (code "82") (name "Net-(U100-A4)") (class "Default")
      (node (ref "R100") (pin "1") (pinfunction "1_1") (pintype "passive"))
      (node (ref "U100") (pin "7") (pinfunction "A4_7") (pintype "passive"))
    )
    (net (code "83") (name "Net-(U100-E1)") (class "Default")
      (node (ref "RN4") (pin "1") (pinfunction "1_1") (pintype "passive"))
      (node (ref "SJ103") (pin "3") (pinfunction "3_3") (pintype "passive"))
      (node (ref "U100") (pin "15") (pinfunction "E1_15") (pintype "passive"))
    )
    (net (code "84") (name "Net-(U100-E2)") (class "Default")
      (node (ref "RN4") (pin "2") (pinfunction "2_2") (pintype "passive"))
      (node (ref "SJ102") (pin "3") (pinfunction "3_3") (pintype "passive"))
      (node (ref "U100") (pin "13") (pinfunction "E2_13") (pintype "passive"))
    )
    (net (code "85") (name "Net-(U100-E3)") (class "Default")
      (node (ref "RN4") (pin "3") (pinfunction "3_3") (pintype "passive"))
      (node (ref "SJ101") (pin "3") (pinfunction "3_3") (pintype "passive"))
      (node (ref "U100") (pin "11") (pinfunction "E3_11") (pintype "passive"))
    )
    (net (code "86") (name "Net-(U100-E4)") (class "Default")
      (node (ref "RN4") (pin "4") (pinfunction "4_4") (pintype "passive"))
      (node (ref "SJ100") (pin "3") (pinfunction "3_3") (pintype "passive"))
      (node (ref "U100") (pin "9") (pinfunction "E4_9") (pintype "passive"))
    )
    (net (code "87") (name "Net-(U101-A1)") (class "Default")
      (node (ref "R107") (pin "1") (pinfunction "1_1") (pintype "passive"))
      (node (ref "U101") (pin "1") (pinfunction "A1_1") (pintype "passive"))
    )
    (net (code "88") (name "Net-(U101-A2)") (class "Default")
      (node (ref "R106") (pin "1") (pinfunction "1_1") (pintype "passive"))
      (node (ref "U101") (pin "3") (pinfunction "A2_3") (pintype "passive"))
    )
    (net (code "89") (name "Net-(U101-A3)") (class "Default")
      (node (ref "R105") (pin "1") (pinfunction "1_1") (pintype "passive"))
      (node (ref "U101") (pin "5") (pinfunction "A3_5") (pintype "passive"))
    )
    (net (code "90") (name "Net-(U101-A4)") (class "Default")
      (node (ref "R104") (pin "1") (pinfunction "1_1") (pintype "passive"))
      (node (ref "U101") (pin "7") (pinfunction "A4_7") (pintype "passive"))
    )
    (net (code "91") (name "Net-(U101-E1)") (class "Default")
      (node (ref "RN3") (pin "1") (pinfunction "1_1") (pintype "passive"))
      (node (ref "SJ107") (pin "3") (pinfunction "3_3") (pintype "passive"))
      (node (ref "U101") (pin "15") (pinfunction "E1_15") (pintype "passive"))
    )
    (net (code "92") (name "Net-(U101-E2)") (class "Default")
      (node (ref "RN3") (pin "2") (pinfunction "2_2") (pintype "passive"))
      (node (ref "SJ106") (pin "3") (pinfunction "3_3") (pintype "passive"))
      (node (ref "U101") (pin "13") (pinfunction "E2_13") (pintype "passive"))
    )
    (net (code "93") (name "Net-(U101-E3)") (class "Default")
      (node (ref "RN3") (pin "3") (pinfunction "3_3") (pintype "passive"))
      (node (ref "SJ105") (pin "3") (pinfunction "3_3") (pintype "passive"))
      (node (ref "U101") (pin "11") (pinfunction "E3_11") (pintype "passive"))
    )
    (net (code "94") (name "Net-(U101-E4)") (class "Default")
      (node (ref "RN3") (pin "4") (pinfunction "4_4") (pintype "passive"))
      (node (ref "SJ104") (pin "3") (pinfunction "3_3") (pintype "passive"))
      (node (ref "U101") (pin "9") (pinfunction "E4_9") (pintype "passive"))
    )
    (net (code "95") (name "Net-(U102-A1)") (class "Default")
      (node (ref "R108") (pin "1") (pinfunction "1_1") (pintype "passive"))
      (node (ref "U102") (pin "1") (pinfunction "A1_1") (pintype "passive"))
    )
    (net (code "96") (name "Net-(U102-A2)") (class "Default")
      (node (ref "R109") (pin "1") (pinfunction "1_1") (pintype "passive"))
      (node (ref "U102") (pin "3") (pinfunction "A2_3") (pintype "passive"))
    )
    (net (code "97") (name "Net-(U102-A3)") (class "Default")
      (node (ref "R110") (pin "1") (pinfunction "1_1") (pintype "passive"))
      (node (ref "U102") (pin "5") (pinfunction "A3_5") (pintype "passive"))
    )
    (net (code "98") (name "Net-(U102-A4)") (class "Default")
      (node (ref "R111") (pin "1") (pinfunction "1_1") (pintype "passive"))
      (node (ref "U102") (pin "7") (pinfunction "A4_7") (pintype "passive"))
    )
    (net (code "99") (name "Net-(U102-CO1)") (class "Default")
      (node (ref "SJ115") (pin "3") (pinfunction "3_3") (pintype "passive"))
      (node (ref "U102") (pin "10") (pinfunction "CO4_10") (pintype "passive"))
      (node (ref "U102") (pin "12") (pinfunction "CO3_12") (pintype "passive"))
      (node (ref "U102") (pin "14") (pinfunction "CO2_14") (pintype "passive"))
      (node (ref "U102") (pin "16") (pinfunction "CO1_16") (pintype "passive"))
    )
    (net (code "100") (name "Net-(U102-E1)") (class "Default")
      (node (ref "RN2") (pin "1") (pinfunction "1_1") (pintype "passive"))
      (node (ref "SJ108") (pin "2") (pinfunction "2_2") (pintype "passive"))
      (node (ref "U102") (pin "15") (pinfunction "E1_15") (pintype "passive"))
    )
    (net (code "101") (name "Net-(U102-E2)") (class "Default")
      (node (ref "RN2") (pin "2") (pinfunction "2_2") (pintype "passive"))
      (node (ref "SJ109") (pin "2") (pinfunction "2_2") (pintype "passive"))
      (node (ref "U102") (pin "13") (pinfunction "E2_13") (pintype "passive"))
    )
    (net (code "102") (name "Net-(U102-E3)") (class "Default")
      (node (ref "RN2") (pin "3") (pinfunction "3_3") (pintype "passive"))
      (node (ref "SJ110") (pin "2") (pinfunction "2_2") (pintype "passive"))
      (node (ref "U102") (pin "11") (pinfunction "E3_11") (pintype "passive"))
    )
    (net (code "103") (name "Net-(U102-E4)") (class "Default")
      (node (ref "RN2") (pin "4") (pinfunction "4_4") (pintype "passive"))
      (node (ref "SJ111") (pin "2") (pinfunction "2_2") (pintype "passive"))
      (node (ref "U102") (pin "9") (pinfunction "E4_9") (pintype "passive"))
    )
    (net (code "104") (name "Net-(U103-A1)") (class "Default")
      (node (ref "R112") (pin "1") (pinfunction "1_1") (pintype "passive"))
      (node (ref "U103") (pin "1") (pinfunction "A1_1") (pintype "passive"))
    )
    (net (code "105") (name "Net-(U103-A2)") (class "Default")
      (node (ref "R113") (pin "1") (pinfunction "1_1") (pintype "passive"))
      (node (ref "U103") (pin "3") (pinfunction "A2_3") (pintype "passive"))
    )
    (net (code "106") (name "Net-(U103-A3)") (class "Default")
      (node (ref "R114") (pin "1") (pinfunction "1_1") (pintype "passive"))
      (node (ref "U103") (pin "5") (pinfunction "A3_5") (pintype "passive"))
    )
    (net (code "107") (name "Net-(U103-A4)") (class "Default")
      (node (ref "R115") (pin "1") (pinfunction "1_1") (pintype "passive"))
      (node (ref "U103") (pin "7") (pinfunction "A4_7") (pintype "passive"))
    )
    (net (code "108") (name "Net-(U103-CO1)") (class "Default")
      (node (ref "SJ117") (pin "3") (pinfunction "3_3") (pintype "passive"))
      (node (ref "U103") (pin "10") (pinfunction "CO4_10") (pintype "passive"))
      (node (ref "U103") (pin "12") (pinfunction "CO3_12") (pintype "passive"))
      (node (ref "U103") (pin "14") (pinfunction "CO2_14") (pintype "passive"))
      (node (ref "U103") (pin "16") (pinfunction "CO1_16") (pintype "passive"))
    )
    (net (code "109") (name "Net-(U103-E1)") (class "Default")
      (node (ref "RN1") (pin "1") (pinfunction "1_1") (pintype "passive"))
      (node (ref "SJ112") (pin "2") (pinfunction "2_2") (pintype "passive"))
      (node (ref "U103") (pin "15") (pinfunction "E1_15") (pintype "passive"))
    )
    (net (code "110") (name "Net-(U103-E2)") (class "Default")
      (node (ref "RN1") (pin "2") (pinfunction "2_2") (pintype "passive"))
      (node (ref "SJ113") (pin "2") (pinfunction "2_2") (pintype "passive"))
      (node (ref "U103") (pin "13") (pinfunction "E2_13") (pintype "passive"))
    )
    (net (code "111") (name "Net-(U103-E3)") (class "Default")
      (node (ref "RN1") (pin "3") (pinfunction "3_3") (pintype "passive"))
      (node (ref "SJ114") (pin "2") (pinfunction "2_2") (pintype "passive"))
      (node (ref "U103") (pin "11") (pinfunction "E3_11") (pintype "passive"))
    )
    (net (code "112") (name "Net-(U103-E4)") (class "Default")
      (node (ref "RN1") (pin "4") (pinfunction "4_4") (pintype "passive"))
      (node (ref "SJ116") (pin "2") (pinfunction "2_2") (pintype "passive"))
      (node (ref "U103") (pin "9") (pinfunction "E4_9") (pintype "passive"))
    )
    (net (code "113") (name "OUTPUT_1") (class "Default")
      (node (ref "SJ116") (pin "1") (pinfunction "1_1") (pintype "passive"))
      (node (ref "U1") (pin "18") (pinfunction "1C_18") (pintype "output"))
    )
    (net (code "114") (name "OUTPUT_2") (class "Default")
      (node (ref "SJ114") (pin "1") (pinfunction "1_1") (pintype "passive"))
      (node (ref "U1") (pin "17") (pinfunction "2C_17") (pintype "output"))
    )
    (net (code "115") (name "OUTPUT_3") (class "Default")
      (node (ref "SJ113") (pin "1") (pinfunction "1_1") (pintype "passive"))
      (node (ref "U1") (pin "16") (pinfunction "3C_16") (pintype "output"))
    )
    (net (code "116") (name "OUTPUT_4") (class "Default")
      (node (ref "SJ112") (pin "1") (pinfunction "1_1") (pintype "passive"))
      (node (ref "U1") (pin "15") (pinfunction "4C_15") (pintype "output"))
    )
    (net (code "117") (name "OUTPUT_5") (class "Default")
      (node (ref "SJ111") (pin "1") (pinfunction "1_1") (pintype "passive"))
      (node (ref "U1") (pin "14") (pinfunction "5C_14") (pintype "output"))
    )
    (net (code "118") (name "OUTPUT_6") (class "Default")
      (node (ref "SJ110") (pin "1") (pinfunction "1_1") (pintype "passive"))
      (node (ref "U1") (pin "13") (pinfunction "6C_13") (pintype "output"))
    )
    (net (code "119") (name "OUTPUT_7") (class "Default")
      (node (ref "SJ109") (pin "1") (pinfunction "1_1") (pintype "passive"))
      (node (ref "U1") (pin "12") (pinfunction "7C_12") (pintype "output"))
    )
    (net (code "120") (name "OUTPUT_8") (class "Default")
      (node (ref "SJ108") (pin "1") (pinfunction "1_1") (pintype "passive"))
      (node (ref "U1") (pin "11") (pinfunction "8C_11") (pintype "output"))
    )
    (net (code "121") (name "OUT_1") (class "Default")
      (node (ref "J1") (pin "1") (pinfunction "1_1") (pintype "passive"))
      (node (ref "R1") (pin "2") (pinfunction "2_2") (pintype "passive"))
      (node (ref "R115") (pin "2") (pinfunction "2_2") (pintype "passive"))
    )
    (net (code "122") (name "OUT_2") (class "Default")
      (node (ref "J1") (pin "2") (pinfunction "2_2") (pintype "passive"))
      (node (ref "R114") (pin "2") (pinfunction "2_2") (pintype "passive"))
      (node (ref "R2") (pin "2") (pinfunction "2_2") (pintype "passive"))
    )
    (net (code "123") (name "OUT_3") (class "Default")
      (node (ref "J1") (pin "3") (pinfunction "3_3") (pintype "passive"))
      (node (ref "R113") (pin "2") (pinfunction "2_2") (pintype "passive"))
      (node (ref "R3") (pin "2") (pinfunction "2_2") (pintype "passive"))
    )
    (net (code "124") (name "OUT_4") (class "Default")
      (node (ref "J1") (pin "4") (pinfunction "4_4") (pintype "passive"))
      (node (ref "R112") (pin "2") (pinfunction "2_2") (pintype "passive"))
      (node (ref "R4") (pin "2") (pinfunction "2_2") (pintype "passive"))
    )
    (net (code "125") (name "OUT_5") (class "Default")
      (node (ref "J1") (pin "5") (pinfunction "5_5") (pintype "passive"))
      (node (ref "R111") (pin "2") (pinfunction "2_2") (pintype "passive"))
      (node (ref "R5") (pin "2") (pinfunction "2_2") (pintype "passive"))
    )
    (net (code "126") (name "OUT_6") (class "Default")
      (node (ref "J1") (pin "6") (pinfunction "6_6") (pintype "passive"))
      (node (ref "R110") (pin "2") (pinfunction "2_2") (pintype "passive"))
      (node (ref "R6") (pin "2") (pinfunction "2_2") (pintype "passive"))
    )
    (net (code "127") (name "OUT_7") (class "Default")
      (node (ref "J1") (pin "7") (pinfunction "7_7") (pintype "passive"))
      (node (ref "R109") (pin "2") (pinfunction "2_2") (pintype "passive"))
      (node (ref "R7") (pin "2") (pinfunction "2_2") (pintype "passive"))
    )
    (net (code "128") (name "OUT_8") (class "Default")
      (node (ref "J1") (pin "8") (pinfunction "8_8") (pintype "passive"))
      (node (ref "R108") (pin "2") (pinfunction "2_2") (pintype "passive"))
      (node (ref "R8") (pin "2") (pinfunction "2_2") (pintype "passive"))
    )
    (net (code "129") (name "SCK") (class "Default")
      (node (ref "IC100") (pin "12") (pinfunction "SCK_12") (pintype "input"))
      (node (ref "J9") (pin "4") (pinfunction "4_4") (pintype "passive"))
    )
    (net (code "130") (name "VCC") (class "Default")
      (node (ref "J1") (pin "11") (pinfunction "11_11") (pintype "passive"))
      (node (ref "J1") (pin "12") (pinfunction "12_12") (pintype "passive"))
      (node (ref "J12") (pin "11") (pinfunction "11_11") (pintype "passive"))
      (node (ref "J12") (pin "12") (pinfunction "12_12") (pintype "passive"))
      (node (ref "U100") (pin "10") (pinfunction "CO4_10") (pintype "passive"))
      (node (ref "U100") (pin "12") (pinfunction "CO3_12") (pintype "passive"))
      (node (ref "U100") (pin "14") (pinfunction "CO2_14") (pintype "passive"))
      (node (ref "U100") (pin "16") (pinfunction "CO1_16") (pintype "passive"))
      (node (ref "U101") (pin "10") (pinfunction "CO4_10") (pintype "passive"))
      (node (ref "U101") (pin "12") (pinfunction "CO3_12") (pintype "passive"))
      (node (ref "U101") (pin "14") (pinfunction "CO2_14") (pintype "passive"))
      (node (ref "U101") (pin "16") (pinfunction "CO1_16") (pintype "passive"))
    )
    (net (code "131") (name "VCCA") (class "Default")
      (node (ref "IC100") (pin "18") (pinfunction "~{RESET}_18") (pintype "input"))
      (node (ref "IC100") (pin "9") (pinfunction "VDD_9") (pintype "power_in"))
      (node (ref "J5") (pin "4") (pinfunction "4_4") (pintype "passive"))
      (node (ref "J5") (pin "5") (pinfunction "5_5") (pintype "passive"))
      (node (ref "J5") (pin "9") (pinfunction "9_9") (pintype "passive"))
      (node (ref "R10") (pin "2") (pinfunction "2_2") (pintype "passive"))
      (node (ref "R11") (pin "2") (pinfunction "2_2") (pintype "passive"))
      (node (ref "R9") (pin "2") (pinfunction "2_2") (pintype "passive"))
      (node (ref "SJ1") (pin "1") (pinfunction "1_1") (pintype "passive"))
      (node (ref "SJ115") (pin "1") (pinfunction "1_1") (pintype "passive"))
      (node (ref "SJ117") (pin "1") (pinfunction "1_1") (pintype "passive"))
    )
    (net (code "132") (name "unconnected-(H1-MOUNT-PadB3,0)") (class "Default")
      (node (ref "H1") (pin "B3,0") (pinfunction "MOUNT_B3,0") (pintype "passive"))
    )
    (net (code "133") (name "unconnected-(H2-MOUNT-PadB3,0)") (class "Default")
      (node (ref "H2") (pin "B3,0") (pinfunction "MOUNT_B3,0") (pintype "passive"))
    )
    (net (code "134") (name "unconnected-(H3-MOUNT-PadB3,0)") (class "Default")
      (node (ref "H3") (pin "B3,0") (pinfunction "MOUNT_B3,0") (pintype "passive"))
    )
    (net (code "135") (name "unconnected-(H4-MOUNT-PadB3,0)") (class "Default")
      (node (ref "H4") (pin "B3,0") (pinfunction "MOUNT_B3,0") (pintype "passive"))
    )
    (net (code "136") (name "unconnected-(IC100-INTA-Pad20)") (class "Default")
      (node (ref "IC100") (pin "20") (pinfunction "INTA_20") (pintype "output"))
    )
    (net (code "137") (name "unconnected-(IC100-INTB-Pad19)") (class "Default")
      (node (ref "IC100") (pin "19") (pinfunction "INTB_19") (pintype "output"))
    )
    (net (code "138") (name "unconnected-(K1-Pad12)") (class "Default")
      (node (ref "K1") (pin "12") (pinfunction "12_12") (pintype "passive"))
    )
    (net (code "139") (name "unconnected-(K2-Pad12)") (class "Default")
      (node (ref "K2") (pin "12") (pinfunction "12_12") (pintype "passive"))
    )
    (net (code "140") (name "unconnected-(K3-Pad12)") (class "Default")
      (node (ref "K3") (pin "12") (pinfunction "12_12") (pintype "passive"))
    )
    (net (code "141") (name "unconnected-(K4-Pad12)") (class "Default")
      (node (ref "K4") (pin "12") (pinfunction "12_12") (pintype "passive"))
    )
    (net (code "142") (name "unconnected-(K5-Pad12)") (class "Default")
      (node (ref "K5") (pin "12") (pinfunction "12_12") (pintype "passive"))
    )
    (net (code "143") (name "unconnected-(K6-Pad12)") (class "Default")
      (node (ref "K6") (pin "12") (pinfunction "12_12") (pintype "passive"))
    )
    (net (code "144") (name "unconnected-(K7-Pad12)") (class "Default")
      (node (ref "K7") (pin "12") (pinfunction "12_12") (pintype "passive"))
    )
    (net (code "145") (name "unconnected-(K8-Pad12)") (class "Default")
      (node (ref "K8") (pin "12") (pinfunction "12_12") (pintype "passive"))
    )
  )
)
